# BUZZER.net
KiCad netlist of a schematic drawn in EAGLE
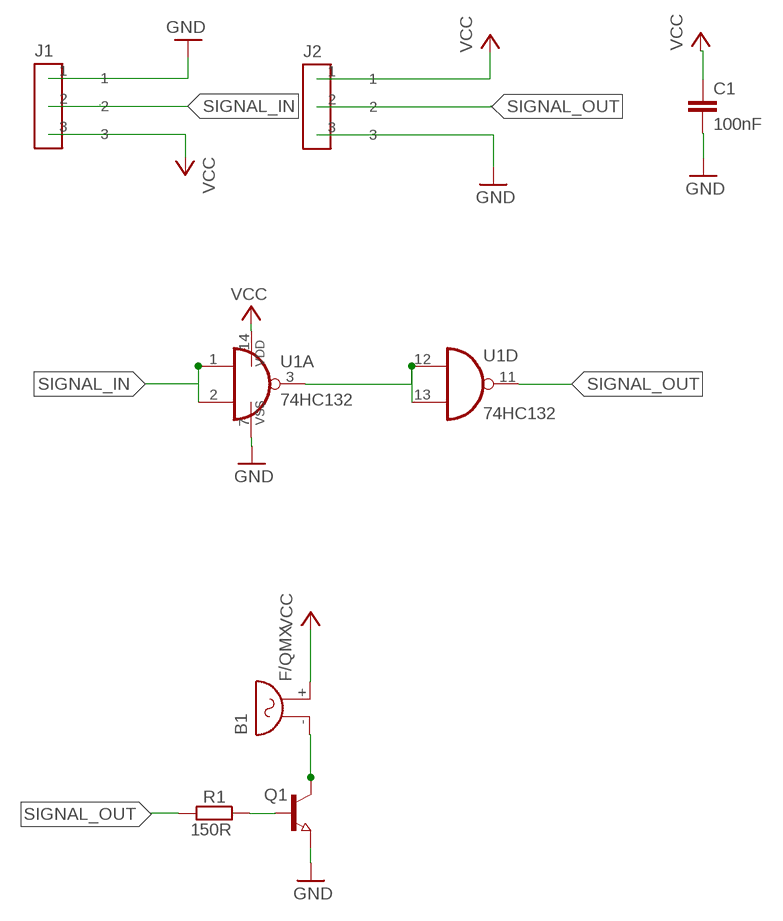
[diagram p0: schematic, sheet 1]

(export (version "E")
  (design (tool "Eeschema 10.0.6"))
  (components
    (comp (ref "B1")
      (value "F/QMX")
      (footprint "eagle-import:F_QMX")
      (libsource (lib "eagle-import") (part "F/QMX"))
    )
    (comp (ref "C1")
      (value "100nF")
      (footprint "eagle-import:C0805")
      (libsource (lib "eagle-import") (part "C-EUC0805"))
    )
    (comp (ref "J1")
      (value "CONECTOR_IN")
      (footprint "eagle-import:3CONECTOR")
      (libsource (lib "eagle-import") (part "CONECTOR_IN"))
    )
    (comp (ref "J2")
      (value "CONECTOR")
      (footprint "eagle-import:3CONECTOR")
      (libsource (lib "eagle-import") (part "CONECTOR"))
    )
    (comp (ref "Q1")
      (value "BC817")
      (footprint "eagle-import:SOT23")
      (libsource (lib "eagle-import") (part "NPN-TRANSISTOR_SOT23"))
    )
    (comp (ref "R1")
      (value "150R")
      (footprint "eagle-import:R0805W")
      (libsource (lib "eagle-import") (part "R-EU_R0805W"))
    )
    (comp (ref "U1")
      (value "74HC132")
      (footprint "eagle-import:SO14")
      (libsource (lib "eagle-import") (part "4011D"))
    )
  )
  (nets
    (net (code "1") (name "GND") (class "Default")
      (node (ref "C1") (pin "2") (pinfunction "2_2") (pintype "passive"))
      (node (ref "J1") (pin "1") (pinfunction "1_1") (pintype "bidirectional"))
      (node (ref "J2") (pin "3") (pinfunction "3_3") (pintype "bidirectional"))
      (node (ref "Q1") (pin "2") (pinfunction "E_2") (pintype "passive"))
      (node (ref "U1") (pin "7") (pinfunction "VSS_7") (pintype "power_in"))
    )
    (net (code "2") (name "Net-(B1-1)") (class "Default")
      (node (ref "B1") (pin "-") (pinfunction "1_-") (pintype "passive"))
      (node (ref "Q1") (pin "3") (pinfunction "C_3") (pintype "passive"))
    )
    (net (code "3") (name "Net-(Q1-B)") (class "Default")
      (node (ref "Q1") (pin "1") (pinfunction "B_1") (pintype "passive"))
      (node (ref "R1") (pin "1") (pinfunction "1_1") (pintype "passive"))
    )
    (net (code "4") (name "Net-(U1A-O)") (class "Default")
      (node (ref "U1") (pin "12") (pinfunction "I0_12") (pintype "input"))
      (node (ref "U1") (pin "13") (pinfunction "I1_13") (pintype "input"))
      (node (ref "U1") (pin "3") (pinfunction "O_3") (pintype "output"))
    )
    (net (code "5") (name "SIGNAL_IN") (class "Default")
      (node (ref "J1") (pin "2") (pinfunction "2_2") (pintype "bidirectional"))
      (node (ref "U1") (pin "1") (pinfunction "I0_1") (pintype "input"))
      (node (ref "U1") (pin "2") (pinfunction "I1_2") (pintype "input"))
    )
    (net (code "6") (name "SIGNAL_OUT") (class "Default")
      (node (ref "J2") (pin "2") (pinfunction "2_2") (pintype "bidirectional"))
      (node (ref "R1") (pin "2") (pinfunction "2_2") (pintype "passive"))
      (node (ref "U1") (pin "11") (pinfunction "O_11") (pintype "output"))
    )
    (net (code "7") (name "VCC") (class "Default")
      (node (ref "B1") (pin "+") (pinfunction "2_+") (pintype "passive"))
      (node (ref "C1") (pin "1") (pinfunction "1_1") (pintype "passive"))
      (node (ref "J1") (pin "3") (pinfunction "3_3") (pintype "bidirectional"))
      (node (ref "J2") (pin "1") (pinfunction "1_1") (pintype "bidirectional"))
      (node (ref "U1") (pin "14") (pinfunction "VDD_14") (pintype "power_in"))
    )
  )
)
